# Power_supply2.net
KiCad netlist of a schematic drawn in EAGLE
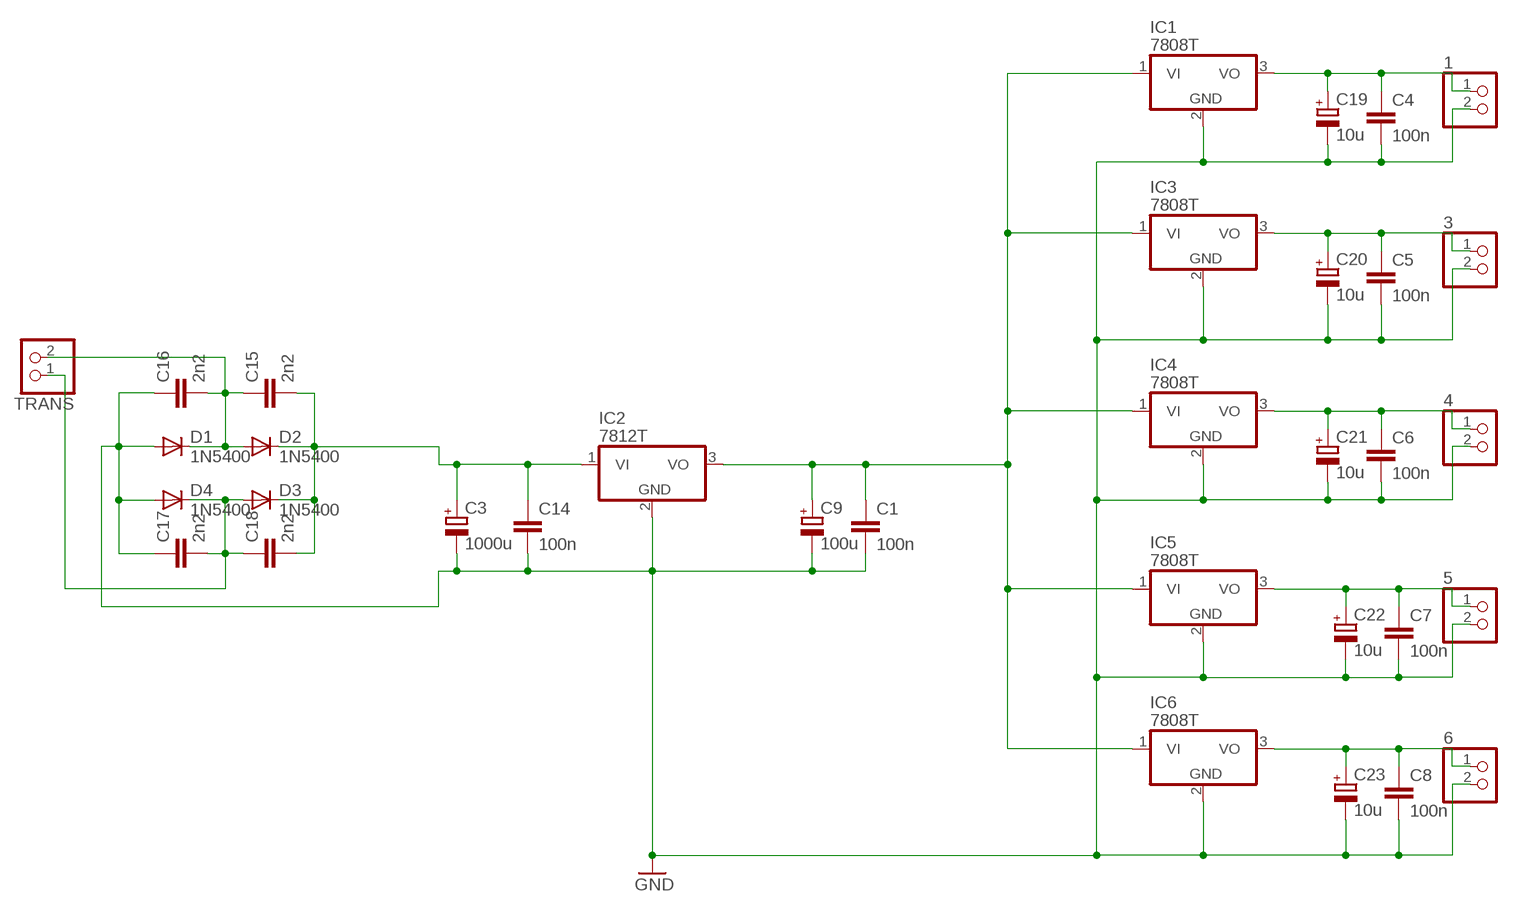
[diagram p0: schematic, sheet 1]

(export (version "E")
  (design (tool "Eeschema 10.0.6"))
  (components
    (comp (ref "1")
      (value "PINHD-1X2")
      (footprint "eagle-import:1X02")
      (libsource (lib "eagle-import") (part "PINHD-1X2"))
    )
    (comp (ref "3")
      (value "PINHD-1X2")
      (footprint "eagle-import:1X02")
      (libsource (lib "eagle-import") (part "PINHD-1X2"))
    )
    (comp (ref "4")
      (value "PINHD-1X2")
      (footprint "eagle-import:1X02")
      (libsource (lib "eagle-import") (part "PINHD-1X2"))
    )
    (comp (ref "5")
      (value "PINHD-1X2")
      (footprint "eagle-import:1X02")
      (libsource (lib "eagle-import") (part "PINHD-1X2"))
    )
    (comp (ref "6")
      (value "PINHD-1X2")
      (footprint "eagle-import:1X02")
      (libsource (lib "eagle-import") (part "PINHD-1X2"))
    )
    (comp (ref "C1")
      (value "100n")
      (footprint "eagle-import:C0805")
      (libsource (lib "eagle-import") (part "C-EUC0805"))
    )
    (comp (ref "C3")
      (value "1000u")
      (footprint "eagle-import:E5-13")
      (libsource (lib "eagle-import") (part "CPOL-EUE5-13"))
    )
    (comp (ref "C4")
      (value "100n")
      (footprint "eagle-import:C0805")
      (libsource (lib "eagle-import") (part "C-EUC0805"))
    )
    (comp (ref "C5")
      (value "100n")
      (footprint "eagle-import:C0805")
      (libsource (lib "eagle-import") (part "C-EUC0805"))
    )
    (comp (ref "C6")
      (value "100n")
      (footprint "eagle-import:C0805")
      (libsource (lib "eagle-import") (part "C-EUC0805"))
    )
    (comp (ref "C7")
      (value "100n")
      (footprint "eagle-import:C0805")
      (libsource (lib "eagle-import") (part "C-EUC0805"))
    )
    (comp (ref "C8")
      (value "100n")
      (footprint "eagle-import:C0805")
      (libsource (lib "eagle-import") (part "C-EUC0805"))
    )
    (comp (ref "C9")
      (value "100u")
      (footprint "eagle-import:E2,5-6")
      (libsource (lib "eagle-import") (part "CPOL-EUE2.5-6"))
    )
    (comp (ref "C14")
      (value "100n")
      (footprint "eagle-import:C0805")
      (libsource (lib "eagle-import") (part "C-EUC0805"))
    )
    (comp (ref "C15")
      (value "2n2")
      (footprint "eagle-import:C0805")
      (libsource (lib "eagle-import") (part "C-EUC0805"))
    )
    (comp (ref "C16")
      (value "2n2")
      (footprint "eagle-import:C0805")
      (libsource (lib "eagle-import") (part "C-EUC0805"))
    )
    (comp (ref "C17")
      (value "2n2")
      (footprint "eagle-import:C0805")
      (libsource (lib "eagle-import") (part "C-EUC0805"))
    )
    (comp (ref "C18")
      (value "2n2")
      (footprint "eagle-import:C0805")
      (libsource (lib "eagle-import") (part "C-EUC0805"))
    )
    (comp (ref "C19")
      (value "10u")
      (footprint "eagle-import:CT7343")
      (libsource (lib "eagle-import") (part "CPOL-EUCT7343"))
    )
    (comp (ref "C20")
      (value "10u")
      (footprint "eagle-import:CT7343")
      (libsource (lib "eagle-import") (part "CPOL-EUCT7343"))
    )
    (comp (ref "C21")
      (value "10u")
      (footprint "eagle-import:CT7343")
      (libsource (lib "eagle-import") (part "CPOL-EUCT7343"))
    )
    (comp (ref "C22")
      (value "10u")
      (footprint "eagle-import:CT7343")
      (libsource (lib "eagle-import") (part "CPOL-EUCT7343"))
    )
    (comp (ref "C23")
      (value "10u")
      (footprint "eagle-import:CT7343")
      (libsource (lib "eagle-import") (part "CPOL-EUCT7343"))
    )
    (comp (ref "D1")
      (value "1N5400")
      (footprint "eagle-import:DO201-15")
      (libsource (lib "eagle-import") (part "1N5400"))
    )
    (comp (ref "D2")
      (value "1N5400")
      (footprint "eagle-import:DO201-15")
      (libsource (lib "eagle-import") (part "1N5400"))
    )
    (comp (ref "D3")
      (value "1N5400")
      (footprint "eagle-import:DO201-15")
      (libsource (lib "eagle-import") (part "1N5400"))
    )
    (comp (ref "D4")
      (value "1N5400")
      (footprint "eagle-import:DO201-15")
      (libsource (lib "eagle-import") (part "1N5400"))
    )
    (comp (ref "IC1")
      (value "7808T")
      (footprint "eagle-import:TO220H")
      (libsource (lib "eagle-import") (part "78T08"))
    )
    (comp (ref "IC2")
      (value "7812T")
      (footprint "eagle-import:TO220H")
      (libsource (lib "eagle-import") (part "78T12"))
    )
    (comp (ref "IC3")
      (value "7808T")
      (footprint "eagle-import:TO220H")
      (libsource (lib "eagle-import") (part "78T08"))
    )
    (comp (ref "IC4")
      (value "7808T")
      (footprint "eagle-import:TO220H")
      (libsource (lib "eagle-import") (part "78T08"))
    )
    (comp (ref "IC5")
      (value "7808T")
      (footprint "eagle-import:TO220H")
      (libsource (lib "eagle-import") (part "78T08"))
    )
    (comp (ref "IC6")
      (value "7808T")
      (footprint "eagle-import:TO220H")
      (libsource (lib "eagle-import") (part "78T08"))
    )
    (comp (ref "TRANS")
      (value "PINHD-1X2")
      (footprint "eagle-import:1X02")
      (libsource (lib "eagle-import") (part "PINHD-1X2"))
    )
  )
  (nets
    (net (code "1") (name "GND") (class "Default")
      (node (ref "1") (pin "2") (pinfunction "2_2") (pintype "passive"))
      (node (ref "3") (pin "2") (pinfunction "2_2") (pintype "passive"))
      (node (ref "4") (pin "2") (pinfunction "2_2") (pintype "passive"))
      (node (ref "5") (pin "2") (pinfunction "2_2") (pintype "passive"))
      (node (ref "6") (pin "2") (pinfunction "2_2") (pintype "passive"))
      (node (ref "C1") (pin "2") (pinfunction "2_2") (pintype "passive"))
      (node (ref "C14") (pin "2") (pinfunction "2_2") (pintype "passive"))
      (node (ref "C16") (pin "1") (pinfunction "1_1") (pintype "passive"))
      (node (ref "C17") (pin "1") (pinfunction "1_1") (pintype "passive"))
      (node (ref "C19") (pin "-") (pinfunction "-_-") (pintype "passive"))
      (node (ref "C20") (pin "-") (pinfunction "-_-") (pintype "passive"))
      (node (ref "C21") (pin "-") (pinfunction "-_-") (pintype "passive"))
      (node (ref "C22") (pin "-") (pinfunction "-_-") (pintype "passive"))
      (node (ref "C23") (pin "-") (pinfunction "-_-") (pintype "passive"))
      (node (ref "C3") (pin "-") (pinfunction "-_-") (pintype "passive"))
      (node (ref "C4") (pin "2") (pinfunction "2_2") (pintype "passive"))
      (node (ref "C5") (pin "2") (pinfunction "2_2") (pintype "passive"))
      (node (ref "C6") (pin "2") (pinfunction "2_2") (pintype "passive"))
      (node (ref "C7") (pin "2") (pinfunction "2_2") (pintype "passive"))
      (node (ref "C8") (pin "2") (pinfunction "2_2") (pintype "passive"))
      (node (ref "C9") (pin "-") (pinfunction "-_-") (pintype "passive"))
      (node (ref "D1") (pin "A") (pinfunction "A_A") (pintype "passive"))
      (node (ref "D4") (pin "A") (pinfunction "A_A") (pintype "passive"))
      (node (ref "IC1") (pin "2") (pinfunction "GND_2") (pintype "passive"))
      (node (ref "IC2") (pin "2") (pinfunction "GND_2") (pintype "passive"))
      (node (ref "IC3") (pin "2") (pinfunction "GND_2") (pintype "passive"))
      (node (ref "IC4") (pin "2") (pinfunction "GND_2") (pintype "passive"))
      (node (ref "IC5") (pin "2") (pinfunction "GND_2") (pintype "passive"))
      (node (ref "IC6") (pin "2") (pinfunction "GND_2") (pintype "passive"))
    )
    (net (code "2") (name "Net-(C15-Pad1)") (class "Default")
      (node (ref "C15") (pin "1") (pinfunction "1_1") (pintype "passive"))
      (node (ref "C16") (pin "2") (pinfunction "2_2") (pintype "passive"))
      (node (ref "D1") (pin "C") (pinfunction "C_C") (pintype "passive"))
      (node (ref "D2") (pin "A") (pinfunction "A_A") (pintype "passive"))
      (node (ref "TRANS") (pin "2") (pinfunction "2_2") (pintype "passive"))
    )
    (net (code "3") (name "Net-(C17-Pad2)") (class "Default")
      (node (ref "C17") (pin "2") (pinfunction "2_2") (pintype "passive"))
      (node (ref "C18") (pin "1") (pinfunction "1_1") (pintype "passive"))
      (node (ref "D3") (pin "A") (pinfunction "A_A") (pintype "passive"))
      (node (ref "D4") (pin "C") (pinfunction "C_C") (pintype "passive"))
      (node (ref "TRANS") (pin "1") (pinfunction "1_1") (pintype "passive"))
    )
    (net (code "4") (name "Net-(IC1-VI)") (class "Default")
      (node (ref "C1") (pin "1") (pinfunction "1_1") (pintype "passive"))
      (node (ref "C9") (pin "+") (pinfunction "+_+") (pintype "passive"))
      (node (ref "IC1") (pin "1") (pinfunction "VI_1") (pintype "input"))
      (node (ref "IC2") (pin "3") (pinfunction "VO_3") (pintype "passive"))
      (node (ref "IC3") (pin "1") (pinfunction "VI_1") (pintype "input"))
      (node (ref "IC4") (pin "1") (pinfunction "VI_1") (pintype "input"))
      (node (ref "IC5") (pin "1") (pinfunction "VI_1") (pintype "input"))
      (node (ref "IC6") (pin "1") (pinfunction "VI_1") (pintype "input"))
    )
    (net (code "5") (name "Net-(IC1-VO)") (class "Default")
      (node (ref "1") (pin "1") (pinfunction "1_1") (pintype "passive"))
      (node (ref "C19") (pin "+") (pinfunction "+_+") (pintype "passive"))
      (node (ref "C4") (pin "1") (pinfunction "1_1") (pintype "passive"))
      (node (ref "IC1") (pin "3") (pinfunction "VO_3") (pintype "passive"))
    )
    (net (code "6") (name "Net-(IC2-VI)") (class "Default")
      (node (ref "C14") (pin "1") (pinfunction "1_1") (pintype "passive"))
      (node (ref "C15") (pin "2") (pinfunction "2_2") (pintype "passive"))
      (node (ref "C18") (pin "2") (pinfunction "2_2") (pintype "passive"))
      (node (ref "C3") (pin "+") (pinfunction "+_+") (pintype "passive"))
      (node (ref "D2") (pin "C") (pinfunction "C_C") (pintype "passive"))
      (node (ref "D3") (pin "C") (pinfunction "C_C") (pintype "passive"))
      (node (ref "IC2") (pin "1") (pinfunction "VI_1") (pintype "input"))
    )
    (net (code "7") (name "Net-(IC3-VO)") (class "Default")
      (node (ref "3") (pin "1") (pinfunction "1_1") (pintype "passive"))
      (node (ref "C20") (pin "+") (pinfunction "+_+") (pintype "passive"))
      (node (ref "C5") (pin "1") (pinfunction "1_1") (pintype "passive"))
      (node (ref "IC3") (pin "3") (pinfunction "VO_3") (pintype "passive"))
    )
    (net (code "8") (name "Net-(IC4-VO)") (class "Default")
      (node (ref "4") (pin "1") (pinfunction "1_1") (pintype "passive"))
      (node (ref "C21") (pin "+") (pinfunction "+_+") (pintype "passive"))
      (node (ref "C6") (pin "1") (pinfunction "1_1") (pintype "passive"))
      (node (ref "IC4") (pin "3") (pinfunction "VO_3") (pintype "passive"))
    )
    (net (code "9") (name "Net-(IC5-VO)") (class "Default")
      (node (ref "5") (pin "1") (pinfunction "1_1") (pintype "passive"))
      (node (ref "C22") (pin "+") (pinfunction "+_+") (pintype "passive"))
      (node (ref "C7") (pin "1") (pinfunction "1_1") (pintype "passive"))
      (node (ref "IC5") (pin "3") (pinfunction "VO_3") (pintype "passive"))
    )
    (net (code "10") (name "Net-(IC6-VO)") (class "Default")
      (node (ref "6") (pin "1") (pinfunction "1_1") (pintype "passive"))
      (node (ref "C23") (pin "+") (pinfunction "+_+") (pintype "passive"))
      (node (ref "C8") (pin "1") (pinfunction "1_1") (pintype "passive"))
      (node (ref "IC6") (pin "3") (pinfunction "VO_3") (pintype "passive"))
    )
  )
)
